# main.net
KiCad netlist of a schematic drawn in EAGLE
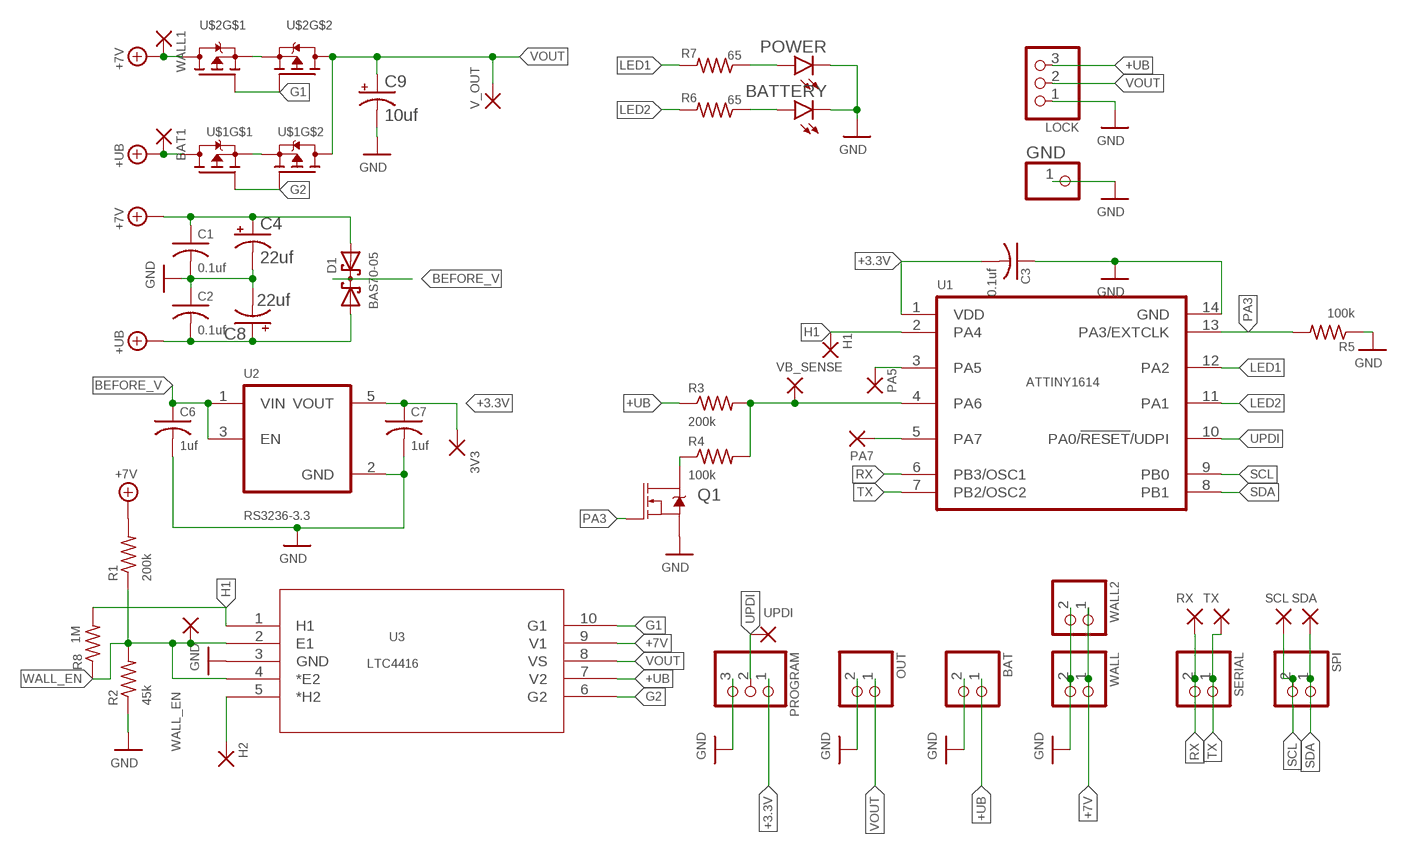
[diagram p0: schematic, sheet 1]

(export (version "E")
  (design (tool "Eeschema 10.0.6"))
  (components
    (comp (ref "3V3")
      (value "SMD2")
      (footprint "eagle-import:SMD1,27-2,54")
      (libsource (lib "eagle-import") (part "SMD2"))
    )
    (comp (ref "BAT")
      (value "PINHD-1X2")
      (footprint "eagle-import:1X02")
      (libsource (lib "eagle-import") (part "PINHD-1X2"))
    )
    (comp (ref "BAT1")
      (value "SMD2")
      (footprint "eagle-import:SMD1,27-2,54")
      (libsource (lib "eagle-import") (part "SMD2"))
    )
    (comp (ref "BATTERY")
      (value "LED5MM")
      (footprint "eagle-import:LED5MM")
      (libsource (lib "eagle-import") (part "LED5MM"))
    )
    (comp (ref "C1")
      (value "0.1uf")
      (footprint "eagle-import:C0805")
      (libsource (lib "eagle-import") (part "C-USC0805"))
    )
    (comp (ref "C2")
      (value "0.1uf")
      (footprint "eagle-import:C0805")
      (libsource (lib "eagle-import") (part "C-USC0805"))
    )
    (comp (ref "C3")
      (value "0.1uf")
      (footprint "eagle-import:C0805")
      (libsource (lib "eagle-import") (part "C-USC0805"))
    )
    (comp (ref "C4")
      (value "22uf")
      (footprint "eagle-import:153CLV-0405")
      (libsource (lib "eagle-import") (part "CPOL-US153CLV-0405"))
    )
    (comp (ref "C6")
      (value "1uf")
      (footprint "eagle-import:C1210")
      (libsource (lib "eagle-import") (part "C-USC1210"))
    )
    (comp (ref "C7")
      (value "1uf")
      (footprint "eagle-import:C1210")
      (libsource (lib "eagle-import") (part "C-USC1210"))
    )
    (comp (ref "C8")
      (value "22uf")
      (footprint "eagle-import:153CLV-0405")
      (libsource (lib "eagle-import") (part "CPOL-US153CLV-0405"))
    )
    (comp (ref "C9")
      (value "10uf")
      (footprint "eagle-import:153CLV-0405")
      (libsource (lib "eagle-import") (part "CPOL-US153CLV-0405"))
    )
    (comp (ref "D1")
      (value "BAS70-05")
      (footprint "eagle-import:SOT23")
      (fields (field (name "MF") "NXP Semiconductors"))
      (libsource (lib "eagle-import") (part "BAS70-05"))
    )
    (comp (ref "GND")
      (value "PINHD-1X1")
      (footprint "eagle-import:1X01")
      (libsource (lib "eagle-import") (part "PINHD-1X1"))
    )
    (comp (ref "H1")
      (value "SMD2")
      (footprint "eagle-import:SMD1,27-2,54")
      (libsource (lib "eagle-import") (part "SMD2"))
    )
    (comp (ref "H2")
      (value "SMD2")
      (footprint "eagle-import:SMD1,27-2,54")
      (libsource (lib "eagle-import") (part "SMD2"))
    )
    (comp (ref "LOCK")
      (value "PINHD-1X3")
      (footprint "eagle-import:1X03")
      (libsource (lib "eagle-import") (part "PINHD-1X3"))
    )
    (comp (ref "OUT")
      (value "PINHD-1X2")
      (footprint "eagle-import:1X02")
      (libsource (lib "eagle-import") (part "PINHD-1X2"))
    )
    (comp (ref "PA5")
      (value "SMD2")
      (footprint "eagle-import:SMD1,27-2,54")
      (libsource (lib "eagle-import") (part "SMD2"))
    )
    (comp (ref "PA7")
      (value "SMD2")
      (footprint "eagle-import:SMD1,27-2,54")
      (libsource (lib "eagle-import") (part "SMD2"))
    )
    (comp (ref "POWER")
      (value "LED5MM")
      (footprint "eagle-import:LED5MM")
      (libsource (lib "eagle-import") (part "LED5MM"))
    )
    (comp (ref "PROGRAM")
      (value "PINHD-1X3")
      (footprint "eagle-import:1X03")
      (libsource (lib "eagle-import") (part "PINHD-1X3"))
    )
    (comp (ref "Q1")
      (value "310mA/60V/1.6Ω")
      (footprint "eagle-import:SOT323")
      (libsource (lib "eagle-import") (part "MOSFET-NCH-2N7002PW"))
    )
    (comp (ref "R1")
      (value "200k")
      (footprint "eagle-import:R0805")
      (libsource (lib "eagle-import") (part "R-US_R0805"))
    )
    (comp (ref "R2")
      (value "45k")
      (footprint "eagle-import:R0805")
      (libsource (lib "eagle-import") (part "R-US_R0805"))
    )
    (comp (ref "R3")
      (value "200k")
      (footprint "eagle-import:R0805")
      (libsource (lib "eagle-import") (part "R-US_R0805"))
    )
    (comp (ref "R4")
      (value "100k")
      (footprint "eagle-import:R0805")
      (libsource (lib "eagle-import") (part "R-US_R0805"))
    )
    (comp (ref "R5")
      (value "100k")
      (footprint "eagle-import:R0805")
      (libsource (lib "eagle-import") (part "R-US_R0805"))
    )
    (comp (ref "R6")
      (value "65")
      (footprint "eagle-import:R0805")
      (libsource (lib "eagle-import") (part "R-US_R0805"))
    )
    (comp (ref "R7")
      (value "65")
      (footprint "eagle-import:R0805")
      (libsource (lib "eagle-import") (part "R-US_R0805"))
    )
    (comp (ref "R8")
      (value "1M")
      (footprint "eagle-import:R0805")
      (libsource (lib "eagle-import") (part "R-US_R0805"))
    )
    (comp (ref "RX")
      (value "SMD2")
      (footprint "eagle-import:SMD1,27-2,54")
      (libsource (lib "eagle-import") (part "SMD2"))
    )
    (comp (ref "SCL")
      (value "SMD2")
      (footprint "eagle-import:SMD1,27-2,54")
      (libsource (lib "eagle-import") (part "SMD2"))
    )
    (comp (ref "SDA")
      (value "SMD2")
      (footprint "eagle-import:SMD1,27-2,54")
      (libsource (lib "eagle-import") (part "SMD2"))
    )
    (comp (ref "SERIAL")
      (value "PINHD-1X2")
      (footprint "eagle-import:1X02")
      (libsource (lib "eagle-import") (part "PINHD-1X2"))
    )
    (comp (ref "SPI")
      (value "PINHD-1X2")
      (footprint "eagle-import:1X02")
      (libsource (lib "eagle-import") (part "PINHD-1X2"))
    )
    (comp (ref "TX")
      (value "SMD2")
      (footprint "eagle-import:SMD1,27-2,54")
      (libsource (lib "eagle-import") (part "SMD2"))
    )
    (comp (ref "U$1")
      (value "IRF7314PBF")
      (footprint "eagle-import:SO-8")
      (fields (field (name "MF") "Infineon"))
      (libsource (lib "eagle-import") (part "IRF7314PBF"))
    )
    (comp (ref "U$2")
      (value "IRF7314PBF")
      (footprint "eagle-import:SO-8")
      (fields (field (name "MF") "Infineon"))
      (libsource (lib "eagle-import") (part "IRF7314PBF"))
    )
    (comp (ref "U1")
      (value "ATTINY1614")
      (footprint "eagle-import:SOIC127P600X175-14N")
      (fields (field (name "MF") "Microchip") (field (name "MP") "ATTINY1614-SSNR"))
      (libsource (lib "eagle-import") (part "ATTINY1614-SSNR"))
    )
    (comp (ref "U2")
      (value "RS3236-3.3")
      (footprint "eagle-import:SOT95P285X140-5N")
      (fields (field (name "MF") "Diodes Inc.") (field (name "MP") "AP2112K-3.3TRG1"))
      (libsource (lib "eagle-import") (part "AP2112K-3.3TRG1"))
    )
    (comp (ref "U3")
      (value "LTC4416")
      (footprint "eagle-import:MSOP-10_MS")
      (fields (field (name "MF") "Analog Devices") (field (name "MP") "LTC4416IMS#PBF"))
      (libsource (lib "eagle-import") (part "LTC4416IMS#PBF"))
    )
    (comp (ref "UPDI")
      (value "SMD2")
      (footprint "eagle-import:SMD1,27-2,54")
      (libsource (lib "eagle-import") (part "SMD2"))
    )
    (comp (ref "VB_SENSE")
      (value "SMD2")
      (footprint "eagle-import:SMD1,27-2,54")
      (libsource (lib "eagle-import") (part "SMD2"))
    )
    (comp (ref "V_OUT")
      (value "SMD2")
      (footprint "eagle-import:SMD1,27-2,54")
      (libsource (lib "eagle-import") (part "SMD2"))
    )
    (comp (ref "WALL")
      (value "PINHD-1X2")
      (footprint "eagle-import:1X02")
      (libsource (lib "eagle-import") (part "PINHD-1X2"))
    )
    (comp (ref "WALL1")
      (value "SMD2")
      (footprint "eagle-import:SMD1,27-2,54")
      (libsource (lib "eagle-import") (part "SMD2"))
    )
    (comp (ref "WALL2")
      (value "PINHD-1X2")
      (footprint "eagle-import:1X02")
      (libsource (lib "eagle-import") (part "PINHD-1X2"))
    )
    (comp (ref "WALL_EN")
      (value "SMD2")
      (footprint "eagle-import:SMD1,27-2,54")
      (libsource (lib "eagle-import") (part "SMD2"))
    )
  )
  (nets
    (net (code "1") (name "+3.3V") (class "Default")
      (node (ref "3V3") (pin "1") (pinfunction "P_1") (pintype "passive"))
      (node (ref "C3") (pin "2") (pinfunction "2_2") (pintype "passive"))
      (node (ref "C7") (pin "1") (pinfunction "1_1") (pintype "passive"))
      (node (ref "PROGRAM") (pin "1") (pinfunction "1_1") (pintype "passive"))
      (node (ref "U1") (pin "1") (pinfunction "VDD_1") (pintype "power_in"))
      (node (ref "U2") (pin "5") (pinfunction "VOUT_5") (pintype "power_in"))
    )
    (net (code "2") (name "+7V") (class "Default")
      (node (ref "C1") (pin "1") (pinfunction "1_1") (pintype "passive"))
      (node (ref "C4") (pin "+") (pinfunction "+_+") (pintype "passive"))
      (node (ref "D1") (pin "2") (pinfunction "A2_2") (pintype "passive"))
      (node (ref "R1") (pin "2") (pinfunction "2_2") (pintype "passive"))
      (node (ref "U$2") (pin "7") (pinfunction "D_7") (pintype "passive"))
      (node (ref "U$2") (pin "8") (pinfunction "D_8") (pintype "passive"))
      (node (ref "U3") (pin "9") (pinfunction "V1_9") (pintype "input"))
      (node (ref "WALL") (pin "1") (pinfunction "1_1") (pintype "passive"))
      (node (ref "WALL1") (pin "1") (pinfunction "P_1") (pintype "passive"))
      (node (ref "WALL2") (pin "1") (pinfunction "1_1") (pintype "passive"))
    )
    (net (code "3") (name "+UB") (class "Default")
      (node (ref "BAT") (pin "1") (pinfunction "1_1") (pintype "passive"))
      (node (ref "BAT1") (pin "1") (pinfunction "P_1") (pintype "passive"))
      (node (ref "C2") (pin "2") (pinfunction "2_2") (pintype "passive"))
      (node (ref "C8") (pin "+") (pinfunction "+_+") (pintype "passive"))
      (node (ref "D1") (pin "1") (pinfunction "A1_1") (pintype "passive"))
      (node (ref "LOCK") (pin "3") (pinfunction "3_3") (pintype "passive"))
      (node (ref "R3") (pin "1") (pinfunction "1_1") (pintype "passive"))
      (node (ref "U$1") (pin "7") (pinfunction "D_7") (pintype "passive"))
      (node (ref "U$1") (pin "8") (pinfunction "D_8") (pintype "passive"))
      (node (ref "U3") (pin "7") (pinfunction "V2_7") (pintype "input"))
    )
    (net (code "4") (name "BEFORE_V") (class "Default")
      (node (ref "C6") (pin "1") (pinfunction "1_1") (pintype "passive"))
      (node (ref "D1") (pin "3") (pinfunction "K1K2_3") (pintype "passive"))
      (node (ref "U2") (pin "1") (pinfunction "VIN_1") (pintype "power_in"))
      (node (ref "U2") (pin "3") (pinfunction "EN_3") (pintype "input"))
    )
    (net (code "5") (name "G1") (class "Default")
      (node (ref "U$2") (pin "2") (pinfunction "G_2") (pintype "passive"))
      (node (ref "U$2") (pin "4") (pinfunction "G_4") (pintype "passive"))
      (node (ref "U3") (pin "10") (pinfunction "G1_10") (pintype "passive"))
    )
    (net (code "6") (name "G2") (class "Default")
      (node (ref "U$1") (pin "2") (pinfunction "G_2") (pintype "passive"))
      (node (ref "U$1") (pin "4") (pinfunction "G_4") (pintype "passive"))
      (node (ref "U3") (pin "6") (pinfunction "G2_6") (pintype "passive"))
    )
    (net (code "7") (name "GND") (class "Default")
      (node (ref "BAT") (pin "2") (pinfunction "2_2") (pintype "passive"))
      (node (ref "BATTERY") (pin "K") (pinfunction "C_K") (pintype "passive"))
      (node (ref "C1") (pin "2") (pinfunction "2_2") (pintype "passive"))
      (node (ref "C2") (pin "1") (pinfunction "1_1") (pintype "passive"))
      (node (ref "C3") (pin "1") (pinfunction "1_1") (pintype "passive"))
      (node (ref "C4") (pin "-") (pinfunction "-_-") (pintype "passive"))
      (node (ref "C6") (pin "2") (pinfunction "2_2") (pintype "passive"))
      (node (ref "C7") (pin "2") (pinfunction "2_2") (pintype "passive"))
      (node (ref "C8") (pin "-") (pinfunction "-_-") (pintype "passive"))
      (node (ref "C9") (pin "-") (pinfunction "-_-") (pintype "passive"))
      (node (ref "GND") (pin "1") (pinfunction "1_1") (pintype "passive"))
      (node (ref "LOCK") (pin "1") (pinfunction "1_1") (pintype "passive"))
      (node (ref "OUT") (pin "2") (pinfunction "2_2") (pintype "passive"))
      (node (ref "POWER") (pin "K") (pinfunction "C_K") (pintype "passive"))
      (node (ref "PROGRAM") (pin "3") (pinfunction "3_3") (pintype "passive"))
      (node (ref "Q1") (pin "2") (pinfunction "S_2") (pintype "bidirectional"))
      (node (ref "R2") (pin "1") (pinfunction "1_1") (pintype "passive"))
      (node (ref "R5") (pin "1") (pinfunction "1_1") (pintype "passive"))
      (node (ref "U1") (pin "14") (pinfunction "GND_14") (pintype "power_in"))
      (node (ref "U2") (pin "2") (pinfunction "GND_2") (pintype "power_in"))
      (node (ref "U3") (pin "3") (pinfunction "GND_3") (pintype "power_in"))
      (node (ref "WALL") (pin "2") (pinfunction "2_2") (pintype "passive"))
      (node (ref "WALL2") (pin "2") (pinfunction "2_2") (pintype "passive"))
    )
    (net (code "8") (name "H1") (class "Default")
      (node (ref "H1") (pin "1") (pinfunction "P_1") (pintype "passive"))
      (node (ref "R8") (pin "2") (pinfunction "2_2") (pintype "passive"))
      (node (ref "U1") (pin "2") (pinfunction "PA4_2") (pintype "bidirectional"))
      (node (ref "U3") (pin "1") (pinfunction "H1_1") (pintype "output"))
    )
    (net (code "9") (name "LED1") (class "Default")
      (node (ref "R7") (pin "2") (pinfunction "2_2") (pintype "passive"))
      (node (ref "U1") (pin "12") (pinfunction "PA2_12") (pintype "bidirectional"))
    )
    (net (code "10") (name "LED2") (class "Default")
      (node (ref "R6") (pin "2") (pinfunction "2_2") (pintype "passive"))
      (node (ref "U1") (pin "11") (pinfunction "PA1_11") (pintype "bidirectional"))
    )
    (net (code "11") (name "Net-(BATTERY-PadA)") (class "Default")
      (node (ref "BATTERY") (pin "A") (pinfunction "A_A") (pintype "passive"))
      (node (ref "R6") (pin "1") (pinfunction "1_1") (pintype "passive"))
    )
    (net (code "12") (name "Net-(H2-P)") (class "Default")
      (node (ref "H2") (pin "1") (pinfunction "P_1") (pintype "passive"))
      (node (ref "U3") (pin "5") (pinfunction "*H2_5") (pintype "input"))
    )
    (net (code "13") (name "Net-(PA5-P)") (class "Default")
      (node (ref "PA5") (pin "1") (pinfunction "P_1") (pintype "passive"))
      (node (ref "U1") (pin "3") (pinfunction "PA5_3") (pintype "bidirectional"))
    )
    (net (code "14") (name "Net-(PA7-P)") (class "Default")
      (node (ref "PA7") (pin "1") (pinfunction "P_1") (pintype "passive"))
      (node (ref "U1") (pin "5") (pinfunction "PA7_5") (pintype "bidirectional"))
    )
    (net (code "15") (name "Net-(POWER-PadA)") (class "Default")
      (node (ref "POWER") (pin "A") (pinfunction "A_A") (pintype "passive"))
      (node (ref "R7") (pin "1") (pinfunction "1_1") (pintype "passive"))
    )
    (net (code "16") (name "Net-(Q1-D)") (class "Default")
      (node (ref "Q1") (pin "3") (pinfunction "D_3") (pintype "bidirectional"))
      (node (ref "R4") (pin "1") (pinfunction "1_1") (pintype "passive"))
    )
    (net (code "17") (name "Net-(U$1A-S)") (class "Default")
      (node (ref "U$1") (pin "1") (pinfunction "S_1") (pintype "passive"))
      (node (ref "U$1") (pin "3") (pinfunction "S_3") (pintype "passive"))
    )
    (net (code "18") (name "Net-(U$2A-S)") (class "Default")
      (node (ref "U$2") (pin "1") (pinfunction "S_1") (pintype "passive"))
      (node (ref "U$2") (pin "3") (pinfunction "S_3") (pintype "passive"))
    )
    (net (code "19") (name "Net-(U1-PA6)") (class "Default")
      (node (ref "R3") (pin "2") (pinfunction "2_2") (pintype "passive"))
      (node (ref "R4") (pin "2") (pinfunction "2_2") (pintype "passive"))
      (node (ref "U1") (pin "4") (pinfunction "PA6_4") (pintype "bidirectional"))
      (node (ref "VB_SENSE") (pin "1") (pinfunction "P_1") (pintype "passive"))
    )
    (net (code "20") (name "PA3") (class "Default")
      (node (ref "Q1") (pin "1") (pinfunction "G_1") (pintype "bidirectional"))
      (node (ref "R5") (pin "2") (pinfunction "2_2") (pintype "passive"))
      (node (ref "U1") (pin "13") (pinfunction "PA3/EXTCLK_13") (pintype "bidirectional"))
    )
    (net (code "21") (name "RX") (class "Default")
      (node (ref "RX") (pin "1") (pinfunction "P_1") (pintype "passive"))
      (node (ref "SERIAL") (pin "2") (pinfunction "2_2") (pintype "passive"))
      (node (ref "U1") (pin "6") (pinfunction "PB3/OSC1_6") (pintype "bidirectional"))
    )
    (net (code "22") (name "SCL") (class "Default")
      (node (ref "SCL") (pin "1") (pinfunction "P_1") (pintype "passive"))
      (node (ref "SPI") (pin "2") (pinfunction "2_2") (pintype "passive"))
      (node (ref "U1") (pin "9") (pinfunction "PB0_9") (pintype "bidirectional"))
    )
    (net (code "23") (name "SDA") (class "Default")
      (node (ref "SDA") (pin "1") (pinfunction "P_1") (pintype "passive"))
      (node (ref "SPI") (pin "1") (pinfunction "1_1") (pintype "passive"))
      (node (ref "U1") (pin "8") (pinfunction "PB1_8") (pintype "bidirectional"))
    )
    (net (code "24") (name "TX") (class "Default")
      (node (ref "SERIAL") (pin "1") (pinfunction "1_1") (pintype "passive"))
      (node (ref "TX") (pin "1") (pinfunction "P_1") (pintype "passive"))
      (node (ref "U1") (pin "7") (pinfunction "PB2/OSC2_7") (pintype "bidirectional"))
    )
    (net (code "25") (name "UPDI") (class "Default")
      (node (ref "PROGRAM") (pin "2") (pinfunction "2_2") (pintype "passive"))
      (node (ref "U1") (pin "10") (pinfunction "PA0/~{RESET}/UDPI_10") (pintype "bidirectional"))
      (node (ref "UPDI") (pin "1") (pinfunction "P_1") (pintype "passive"))
    )
    (net (code "26") (name "VOUT") (class "Default")
      (node (ref "C9") (pin "+") (pinfunction "+_+") (pintype "passive"))
      (node (ref "LOCK") (pin "2") (pinfunction "2_2") (pintype "passive"))
      (node (ref "OUT") (pin "1") (pinfunction "1_1") (pintype "passive"))
      (node (ref "U$1") (pin "5") (pinfunction "D_5") (pintype "passive"))
      (node (ref "U$1") (pin "6") (pinfunction "D_6") (pintype "passive"))
      (node (ref "U$2") (pin "5") (pinfunction "D_5") (pintype "passive"))
      (node (ref "U$2") (pin "6") (pinfunction "D_6") (pintype "passive"))
      (node (ref "U3") (pin "8") (pinfunction "VS_8") (pintype "input"))
      (node (ref "V_OUT") (pin "1") (pinfunction "P_1") (pintype "passive"))
    )
    (net (code "27") (name "WALL_EN") (class "Default")
      (node (ref "R1") (pin "1") (pinfunction "1_1") (pintype "passive"))
      (node (ref "R2") (pin "2") (pinfunction "2_2") (pintype "passive"))
      (node (ref "R8") (pin "1") (pinfunction "1_1") (pintype "passive"))
      (node (ref "U3") (pin "2") (pinfunction "E1_2") (pintype "input"))
      (node (ref "U3") (pin "4") (pinfunction "*E2_4") (pintype "input"))
      (node (ref "WALL_EN") (pin "1") (pinfunction "P_1") (pintype "passive"))
    )
  )
)
